# NixieMicrocontroller.net
KiCad netlist of a schematic drawn in Altium Designer
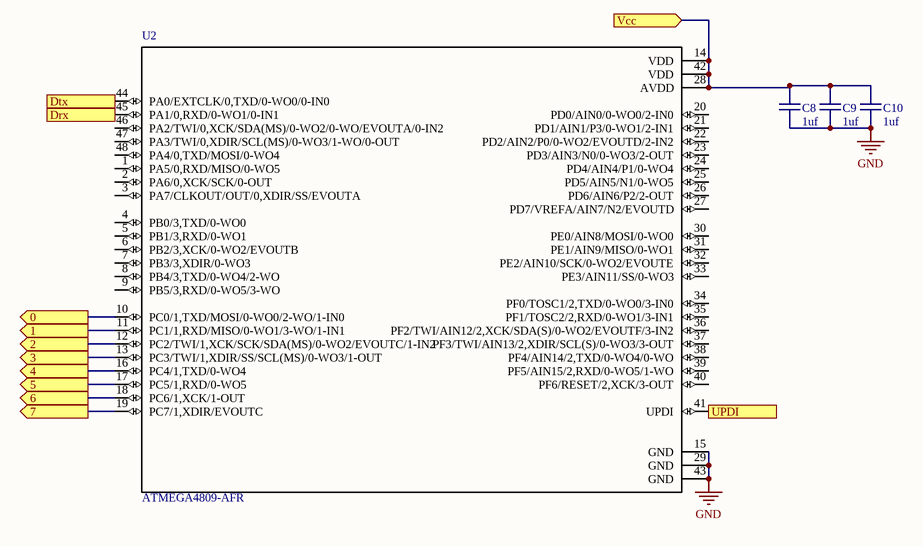
[diagram p0: NixieMicrocontroller.SchDoc]

(export (version "E")
  (design (tool "Eeschema 10.0.6"))
  (components
    (comp (ref "C8")
      (value "1uf")
      (footprint "CAPC0805(2012)100_N")
      (description "X7R 50V")
      (libsource (lib "OVLib_64") (part "CAP"))
    )
    (comp (ref "C9")
      (value "1uf")
      (footprint "CAPC0805(2012)100_N")
      (description "X7R 50V")
      (libsource (lib "OVLib_64") (part "CAP"))
    )
    (comp (ref "C10")
      (value "1uf")
      (footprint "CAPC0805(2012)100_N")
      (description "X7R 50V")
      (libsource (lib "OVLib_64") (part "CAP"))
    )
    (comp (ref "U2")
      (value "ATMEGA4809-AFR")
      (footprint "*QFP50P900X900X120-48N")
      (description "20MHz 48KB TQFP48 Ind 125C Green T&R")
      (fields (field (name "MF") "Microchip"))
      (libsource (lib "ATMEGA4809-AFR") (part "ATMEGA4809-AFR"))
    )
  )
  (nets
    (net (code "1") (name "/0") (class "Default")
      (node (ref "U2") (pin "10") (pinfunction "PC0/1,TXD/MOSI/0-WO0/2-WO/1-IN0_10") (pintype "bidirectional"))
    )
    (net (code "2") (name "/1") (class "Default")
      (node (ref "U2") (pin "11") (pinfunction "PC1/1,RXD/MISO/0-WO1/3-WO/1-IN1_11") (pintype "bidirectional"))
    )
    (net (code "3") (name "/2") (class "Default")
      (node (ref "U2") (pin "12") (pinfunction "PC2/TWI/1,XCK/SCK/SDA(MS)/0-WO2/EVOUTC/1-IN2_12") (pintype "bidirectional"))
    )
    (net (code "4") (name "/3") (class "Default")
      (node (ref "U2") (pin "13") (pinfunction "PC3/TWI/1,XDIR/SS/SCL(MS)/0-WO3/1-OUT_13") (pintype "bidirectional"))
    )
    (net (code "5") (name "/4") (class "Default")
      (node (ref "U2") (pin "16") (pinfunction "PC4/1,TXD/0-WO4_16") (pintype "bidirectional"))
    )
    (net (code "6") (name "/5") (class "Default")
      (node (ref "U2") (pin "17") (pinfunction "PC5/1,RXD/0-WO5_17") (pintype "bidirectional"))
    )
    (net (code "7") (name "/6") (class "Default")
      (node (ref "U2") (pin "18") (pinfunction "PC6/1,XCK/1-OUT_18") (pintype "bidirectional"))
    )
    (net (code "8") (name "/7") (class "Default")
      (node (ref "U2") (pin "19") (pinfunction "PC7/1,XDIR/EVOUTC_19") (pintype "bidirectional"))
    )
    (net (code "9") (name "/Drx") (class "Default")
      (node (ref "U2") (pin "45") (pinfunction "PA1/0,RXD/0-WO1/0-IN1_45") (pintype "bidirectional"))
    )
    (net (code "10") (name "/Dtx") (class "Default")
      (node (ref "U2") (pin "44") (pinfunction "PA0/EXTCLK/0,TXD/0-WO0/0-IN0_44") (pintype "bidirectional"))
    )
    (net (code "11") (name "/UPDI") (class "Default")
      (node (ref "U2") (pin "41") (pinfunction "UPDI_41") (pintype "bidirectional"))
    )
    (net (code "12") (name "/Vcc") (class "Default")
      (node (ref "C10") (pin "2") (pinfunction "2_2") (pintype "passive"))
      (node (ref "C8") (pin "2") (pinfunction "2_2") (pintype "passive"))
      (node (ref "C9") (pin "2") (pinfunction "2_2") (pintype "passive"))
      (node (ref "U2") (pin "14") (pinfunction "VDD_14") (pintype "power_in"))
      (node (ref "U2") (pin "28") (pinfunction "AVDD_28") (pintype "power_in"))
      (node (ref "U2") (pin "42") (pinfunction "VDD_42") (pintype "power_in"))
    )
    (net (code "13") (name "GND") (class "Default")
      (node (ref "C10") (pin "1") (pinfunction "1_1") (pintype "passive"))
      (node (ref "C8") (pin "1") (pinfunction "1_1") (pintype "passive"))
      (node (ref "C9") (pin "1") (pinfunction "1_1") (pintype "passive"))
      (node (ref "U2") (pin "15") (pinfunction "GND_15") (pintype "power_in"))
      (node (ref "U2") (pin "29") (pinfunction "GND_29") (pintype "power_in"))
      (node (ref "U2") (pin "43") (pinfunction "GND_43") (pintype "power_in"))
    )
    (net (code "14") (name "unconnected-(U2-PA2{slash}TWI{slash}0,XCK{slash}SDA(MS){slash}0-WO2{slash}0-WO{slash}EVOUTA{slash}0-IN2-Pad46)") (class "Default")
      (node (ref "U2") (pin "46") (pinfunction "PA2/TWI/0,XCK/SDA(MS)/0-WO2/0-WO/EVOUTA/0-IN2_46") (pintype "bidirectional"))
    )
    (net (code "15") (name "unconnected-(U2-PA3{slash}TWI{slash}0,XDIR{slash}SCL(MS){slash}0-WO3{slash}1-WO{slash}0-OUT-Pad47)") (class "Default")
      (node (ref "U2") (pin "47") (pinfunction "PA3/TWI/0,XDIR/SCL(MS)/0-WO3/1-WO/0-OUT_47") (pintype "bidirectional"))
    )
    (net (code "16") (name "unconnected-(U2-PA4{slash}0,TXD{slash}MOSI{slash}0-WO4-Pad48)") (class "Default")
      (node (ref "U2") (pin "48") (pinfunction "PA4/0,TXD/MOSI/0-WO4_48") (pintype "bidirectional"))
    )
    (net (code "17") (name "unconnected-(U2-PA5{slash}0,RXD{slash}MISO{slash}0-WO5-Pad1)") (class "Default")
      (node (ref "U2") (pin "1") (pinfunction "PA5/0,RXD/MISO/0-WO5_1") (pintype "bidirectional"))
    )
    (net (code "18") (name "unconnected-(U2-PA6{slash}0,XCK{slash}SCK{slash}0-OUT-Pad2)") (class "Default")
      (node (ref "U2") (pin "2") (pinfunction "PA6/0,XCK/SCK/0-OUT_2") (pintype "bidirectional"))
    )
    (net (code "19") (name "unconnected-(U2-PA7{slash}CLKOUT{slash}OUT{slash}0,XDIR{slash}SS{slash}EVOUTA-Pad3)") (class "Default")
      (node (ref "U2") (pin "3") (pinfunction "PA7/CLKOUT/OUT/0,XDIR/SS/EVOUTA_3") (pintype "bidirectional"))
    )
    (net (code "20") (name "unconnected-(U2-PB0{slash}3,TXD{slash}0-WO0-Pad4)") (class "Default")
      (node (ref "U2") (pin "4") (pinfunction "PB0/3,TXD/0-WO0_4") (pintype "bidirectional"))
    )
    (net (code "21") (name "unconnected-(U2-PB1{slash}3,RXD{slash}0-WO1-Pad5)") (class "Default")
      (node (ref "U2") (pin "5") (pinfunction "PB1/3,RXD/0-WO1_5") (pintype "bidirectional"))
    )
    (net (code "22") (name "unconnected-(U2-PB2{slash}3,XCK{slash}0-WO2{slash}EVOUTB-Pad6)") (class "Default")
      (node (ref "U2") (pin "6") (pinfunction "PB2/3,XCK/0-WO2/EVOUTB_6") (pintype "bidirectional"))
    )
    (net (code "23") (name "unconnected-(U2-PB3{slash}3,XDIR{slash}0-WO3-Pad7)") (class "Default")
      (node (ref "U2") (pin "7") (pinfunction "PB3/3,XDIR/0-WO3_7") (pintype "bidirectional"))
    )
    (net (code "24") (name "unconnected-(U2-PB4{slash}3,TXD{slash}0-WO4{slash}2-WO-Pad8)") (class "Default")
      (node (ref "U2") (pin "8") (pinfunction "PB4/3,TXD/0-WO4/2-WO_8") (pintype "bidirectional"))
    )
    (net (code "25") (name "unconnected-(U2-PB5{slash}3,RXD{slash}0-WO5{slash}3-WO-Pad9)") (class "Default")
      (node (ref "U2") (pin "9") (pinfunction "PB5/3,RXD/0-WO5/3-WO_9") (pintype "bidirectional"))
    )
    (net (code "26") (name "unconnected-(U2-PD0{slash}AIN0{slash}0-WO0{slash}2-IN0-Pad20)") (class "Default")
      (node (ref "U2") (pin "20") (pinfunction "PD0/AIN0/0-WO0/2-IN0_20") (pintype "bidirectional"))
    )
    (net (code "27") (name "unconnected-(U2-PD1{slash}AIN1{slash}P3{slash}0-WO1{slash}2-IN1-Pad21)") (class "Default")
      (node (ref "U2") (pin "21") (pinfunction "PD1/AIN1/P3/0-WO1/2-IN1_21") (pintype "bidirectional"))
    )
    (net (code "28") (name "unconnected-(U2-PD2{slash}AIN2{slash}P0{slash}0-WO2{slash}EVOUTD{slash}2-IN2-Pad22)") (class "Default")
      (node (ref "U2") (pin "22") (pinfunction "PD2/AIN2/P0/0-WO2/EVOUTD/2-IN2_22") (pintype "bidirectional"))
    )
    (net (code "29") (name "unconnected-(U2-PD3{slash}AIN3{slash}N0{slash}0-WO3{slash}2-OUT-Pad23)") (class "Default")
      (node (ref "U2") (pin "23") (pinfunction "PD3/AIN3/N0/0-WO3/2-OUT_23") (pintype "bidirectional"))
    )
    (net (code "30") (name "unconnected-(U2-PD4{slash}AIN4{slash}P1{slash}0-WO4-Pad24)") (class "Default")
      (node (ref "U2") (pin "24") (pinfunction "PD4/AIN4/P1/0-WO4_24") (pintype "bidirectional"))
    )
    (net (code "31") (name "unconnected-(U2-PD5{slash}AIN5{slash}N1{slash}0-WO5-Pad25)") (class "Default")
      (node (ref "U2") (pin "25") (pinfunction "PD5/AIN5/N1/0-WO5_25") (pintype "bidirectional"))
    )
    (net (code "32") (name "unconnected-(U2-PD6{slash}AIN6{slash}P2{slash}2-OUT-Pad26)") (class "Default")
      (node (ref "U2") (pin "26") (pinfunction "PD6/AIN6/P2/2-OUT_26") (pintype "bidirectional"))
    )
    (net (code "33") (name "unconnected-(U2-PD7{slash}VREFA{slash}AIN7{slash}N2{slash}EVOUTD-Pad27)") (class "Default")
      (node (ref "U2") (pin "27") (pinfunction "PD7/VREFA/AIN7/N2/EVOUTD_27") (pintype "bidirectional"))
    )
    (net (code "34") (name "unconnected-(U2-PE0{slash}AIN8{slash}MOSI{slash}0-WO0-Pad30)") (class "Default")
      (node (ref "U2") (pin "30") (pinfunction "PE0/AIN8/MOSI/0-WO0_30") (pintype "bidirectional"))
    )
    (net (code "35") (name "unconnected-(U2-PE1{slash}AIN9{slash}MISO{slash}0-WO1-Pad31)") (class "Default")
      (node (ref "U2") (pin "31") (pinfunction "PE1/AIN9/MISO/0-WO1_31") (pintype "bidirectional"))
    )
    (net (code "36") (name "unconnected-(U2-PE2{slash}AIN10{slash}SCK{slash}0-WO2{slash}EVOUTE-Pad32)") (class "Default")
      (node (ref "U2") (pin "32") (pinfunction "PE2/AIN10/SCK/0-WO2/EVOUTE_32") (pintype "bidirectional"))
    )
    (net (code "37") (name "unconnected-(U2-PE3{slash}AIN11{slash}SS{slash}0-WO3-Pad33)") (class "Default")
      (node (ref "U2") (pin "33") (pinfunction "PE3/AIN11/SS/0-WO3_33") (pintype "bidirectional"))
    )
    (net (code "38") (name "unconnected-(U2-PF0{slash}TOSC1{slash}2,TXD{slash}0-WO0{slash}3-IN0-Pad34)") (class "Default")
      (node (ref "U2") (pin "34") (pinfunction "PF0/TOSC1/2,TXD/0-WO0/3-IN0_34") (pintype "bidirectional"))
    )
    (net (code "39") (name "unconnected-(U2-PF1{slash}TOSC2{slash}2,RXD{slash}0-WO1{slash}3-IN1-Pad35)") (class "Default")
      (node (ref "U2") (pin "35") (pinfunction "PF1/TOSC2/2,RXD/0-WO1/3-IN1_35") (pintype "bidirectional"))
    )
    (net (code "40") (name "unconnected-(U2-PF2{slash}TWI{slash}AIN12{slash}2,XCK{slash}SDA(S){slash}0-WO2{slash}EVOUTF{slash}3-IN2-Pad36)") (class "Default")
      (node (ref "U2") (pin "36") (pinfunction "PF2/TWI/AIN12/2,XCK/SDA(S)/0-WO2/EVOUTF/3-IN2_36") (pintype "bidirectional"))
    )
    (net (code "41") (name "unconnected-(U2-PF3{slash}TWI{slash}AIN13{slash}2,XDIR{slash}SCL(S){slash}0-WO3{slash}3-OUT-Pad37)") (class "Default")
      (node (ref "U2") (pin "37") (pinfunction "PF3/TWI/AIN13/2,XDIR/SCL(S)/0-WO3/3-OUT_37") (pintype "bidirectional"))
    )
    (net (code "42") (name "unconnected-(U2-PF4{slash}AIN14{slash}2,TXD{slash}0-WO4{slash}0-WO-Pad38)") (class "Default")
      (node (ref "U2") (pin "38") (pinfunction "PF4/AIN14/2,TXD/0-WO4/0-WO_38") (pintype "bidirectional"))
    )
    (net (code "43") (name "unconnected-(U2-PF5{slash}AIN15{slash}2,RXD{slash}0-WO5{slash}1-WO-Pad39)") (class "Default")
      (node (ref "U2") (pin "39") (pinfunction "PF5/AIN15/2,RXD/0-WO5/1-WO_39") (pintype "bidirectional"))
    )
    (net (code "44") (name "unconnected-(U2-PF6{slash}RESET{slash}2,XCK{slash}3-OUT-Pad40)") (class "Default")
      (node (ref "U2") (pin "40") (pinfunction "PF6/RESET/2,XCK/3-OUT_40") (pintype "bidirectional"))
    )
  )
)
